# wifi-power.net
KiCad netlist of a schematic drawn in EAGLE
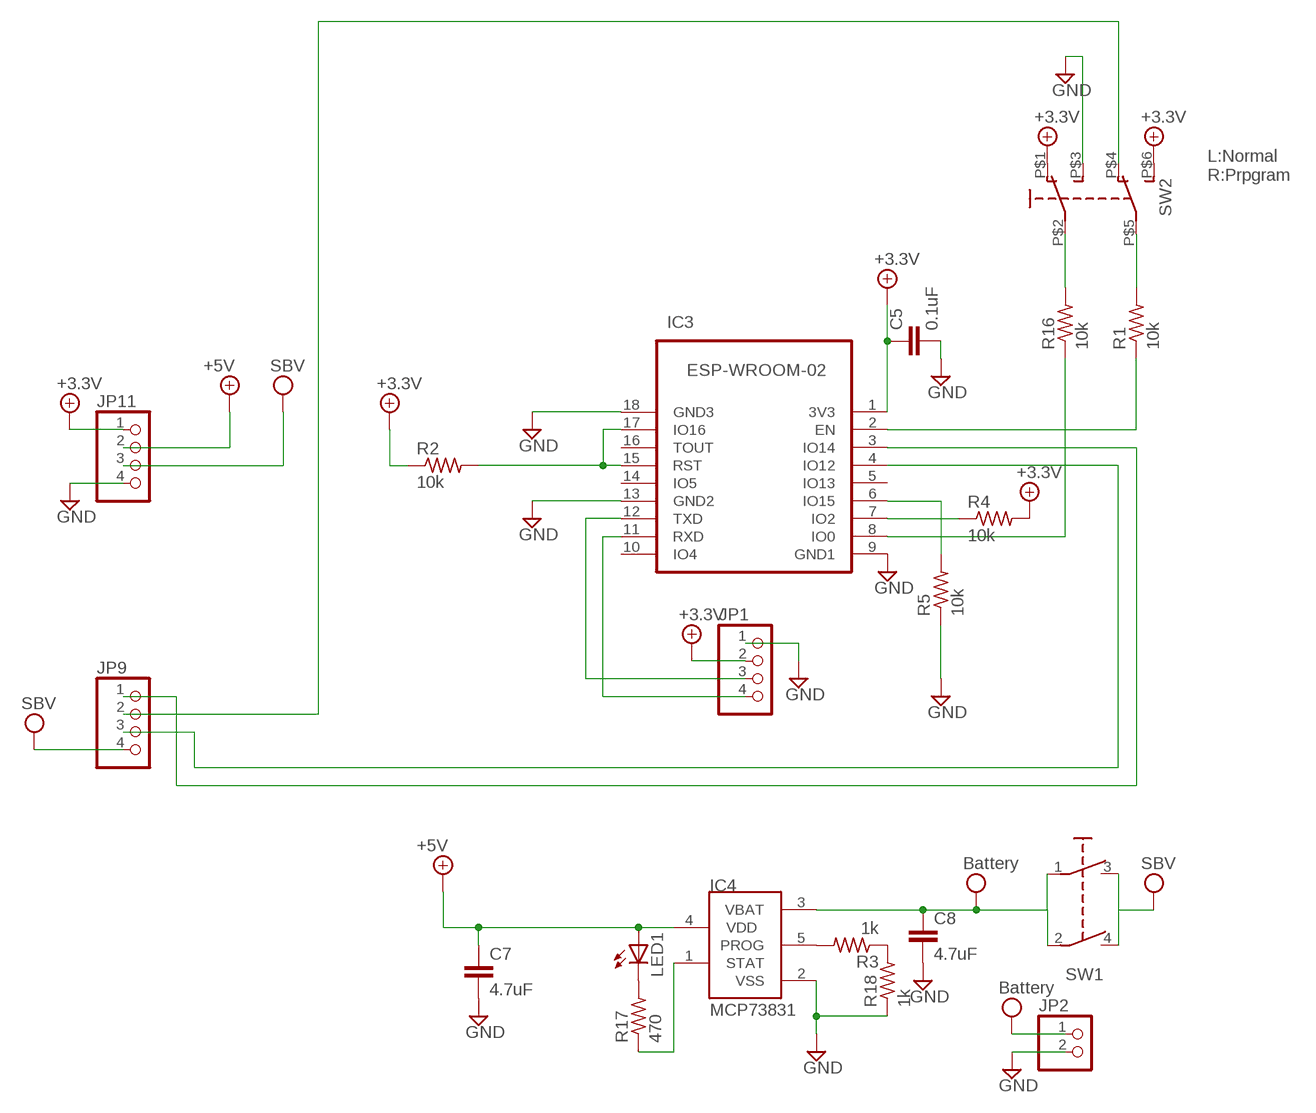
[diagram p0: schematic, sheet 1]

(export (version "E")
  (design (tool "Eeschema 10.0.6"))
  (components
    (comp (ref "C5")
      (value "0.1uF")
      (footprint "eagle-import:C0603K")
      (libsource (lib "eagle-import") (part "C-EUC0603K"))
    )
    (comp (ref "C7")
      (value "4.7uF")
      (footprint "eagle-import:C0603K")
      (libsource (lib "eagle-import") (part "C-EUC0603K"))
    )
    (comp (ref "C8")
      (value "4.7uF")
      (footprint "eagle-import:C0603K")
      (libsource (lib "eagle-import") (part "C-EUC0603K"))
    )
    (comp (ref "IC3")
      (value "ESP-WROOM-02")
      (footprint "eagle-import:FRONT-FACE")
      (libsource (lib "eagle-import") (part "ESP-WROOM-02FRONT-FACE"))
    )
    (comp (ref "IC4")
      (value "MCP73831")
      (footprint "eagle-import:SOT23-5L")
      (libsource (lib "eagle-import") (part "MCP73831"))
    )
    (comp (ref "JP1")
      (value "PINHD-1X4")
      (footprint "eagle-import:1X04")
      (libsource (lib "eagle-import") (part "PINHD-1X4"))
    )
    (comp (ref "JP2")
      (value "PINHD-1X2")
      (footprint "eagle-import:1X02")
      (libsource (lib "eagle-import") (part "PINHD-1X2"))
    )
    (comp (ref "JP9")
      (value "PINHD-1X4")
      (footprint "eagle-import:1X04")
      (libsource (lib "eagle-import") (part "PINHD-1X4"))
    )
    (comp (ref "JP11")
      (value "PINHD-1X4")
      (footprint "eagle-import:1X04")
      (libsource (lib "eagle-import") (part "PINHD-1X4"))
    )
    (comp (ref "LED1")
      (value "LG_T679-E1F1-1")
      (footprint "eagle-import:PLCC2")
      (libsource (lib "eagle-import") (part "_T679-?-1E1F1LG"))
    )
    (comp (ref "R1")
      (value "10k")
      (footprint "eagle-import:M0805")
      (libsource (lib "eagle-import") (part "R-US_M0805"))
    )
    (comp (ref "R2")
      (value "10k")
      (footprint "eagle-import:M0805")
      (libsource (lib "eagle-import") (part "R-US_M0805"))
    )
    (comp (ref "R3")
      (value "1k")
      (footprint "eagle-import:MINI_MELF-0102R")
      (libsource (lib "eagle-import") (part "R-US_MELF0102R"))
    )
    (comp (ref "R4")
      (value "10k")
      (footprint "eagle-import:M0805")
      (libsource (lib "eagle-import") (part "R-US_M0805"))
    )
    (comp (ref "R5")
      (value "10k")
      (footprint "eagle-import:M0805")
      (libsource (lib "eagle-import") (part "R-US_M0805"))
    )
    (comp (ref "R16")
      (value "10k")
      (footprint "eagle-import:M0805")
      (libsource (lib "eagle-import") (part "R-US_M0805"))
    )
    (comp (ref "R17")
      (value "470")
      (footprint "eagle-import:M0805")
      (libsource (lib "eagle-import") (part "R-US_M0805"))
    )
    (comp (ref "R18")
      (value "1k")
      (footprint "eagle-import:MINI_MELF-0102R")
      (libsource (lib "eagle-import") (part "R-US_MELF0102R"))
    )
    (comp (ref "SW1")
      (value "2X1S-SIDE-0.1INCH")
      (footprint "eagle-import:2X1SIDE-0.1INCH")
      (libsource (lib "eagle-import") (part "2X1S-SIDE-0.1INCH"))
    )
    (comp (ref "SW2")
      (value "MSS-22C02")
      (footprint "eagle-import:MSS-22C02")
      (libsource (lib "eagle-import") (part "MSS-22C02"))
    )
  )
  (nets
    (net (code "1") (name "+3.3V") (class "Default")
      (node (ref "C5") (pin "1") (pinfunction "1_1") (pintype "passive"))
      (node (ref "IC3") (pin "1") (pinfunction "3V3_1") (pintype "power_in"))
      (node (ref "JP1") (pin "2") (pinfunction "2_2") (pintype "passive"))
      (node (ref "JP11") (pin "1") (pinfunction "1_1") (pintype "passive"))
      (node (ref "R2") (pin "1") (pinfunction "1_1") (pintype "passive"))
      (node (ref "R4") (pin "2") (pinfunction "2_2") (pintype "passive"))
      (node (ref "SW2") (pin "P$1") (pinfunction "O_P$1") (pintype "passive"))
      (node (ref "SW2") (pin "P$6") (pinfunction "S1_P$6") (pintype "passive"))
    )
    (net (code "2") (name "+5V") (class "Default")
      (node (ref "C7") (pin "1") (pinfunction "1_1") (pintype "passive"))
      (node (ref "IC4") (pin "4") (pinfunction "VDD_4") (pintype "bidirectional"))
      (node (ref "JP11") (pin "2") (pinfunction "2_2") (pintype "passive"))
      (node (ref "LED1") (pin "A") (pinfunction "A_A") (pintype "passive"))
    )
    (net (code "3") (name "Battery") (class "Default")
      (node (ref "C8") (pin "1") (pinfunction "1_1") (pintype "passive"))
      (node (ref "IC4") (pin "3") (pinfunction "VBAT_3") (pintype "bidirectional"))
      (node (ref "JP2") (pin "1") (pinfunction "1_1") (pintype "passive"))
      (node (ref "SW1") (pin "1") (pinfunction "P_1") (pintype "passive"))
      (node (ref "SW1") (pin "2") (pinfunction "P1_2") (pintype "passive"))
    )
    (net (code "4") (name "GND") (class "Default")
      (node (ref "C5") (pin "2") (pinfunction "2_2") (pintype "passive"))
      (node (ref "C7") (pin "2") (pinfunction "2_2") (pintype "passive"))
      (node (ref "C8") (pin "2") (pinfunction "2_2") (pintype "passive"))
      (node (ref "IC3") (pin "13") (pinfunction "GND2_13") (pintype "power_in"))
      (node (ref "IC3") (pin "18") (pinfunction "GND3_18") (pintype "power_in"))
      (node (ref "IC3") (pin "9") (pinfunction "GND1_9") (pintype "power_in"))
      (node (ref "IC4") (pin "2") (pinfunction "VSS_2") (pintype "bidirectional"))
      (node (ref "JP1") (pin "1") (pinfunction "1_1") (pintype "passive"))
      (node (ref "JP11") (pin "4") (pinfunction "4_4") (pintype "passive"))
      (node (ref "JP2") (pin "2") (pinfunction "2_2") (pintype "passive"))
      (node (ref "R18") (pin "1") (pinfunction "1_1") (pintype "passive"))
      (node (ref "R5") (pin "1") (pinfunction "1_1") (pintype "passive"))
      (node (ref "SW2") (pin "P$3") (pinfunction "S_P$3") (pintype "passive"))
    )
    (net (code "5") (name "Net-(IC3-EN)") (class "Default")
      (node (ref "IC3") (pin "2") (pinfunction "EN_2") (pintype "bidirectional"))
      (node (ref "R1") (pin "1") (pinfunction "1_1") (pintype "passive"))
    )
    (net (code "6") (name "Net-(IC3-IO0)") (class "Default")
      (node (ref "IC3") (pin "8") (pinfunction "IO0_8") (pintype "bidirectional"))
      (node (ref "R16") (pin "1") (pinfunction "1_1") (pintype "passive"))
    )
    (net (code "7") (name "Net-(IC3-IO2)") (class "Default")
      (node (ref "IC3") (pin "7") (pinfunction "IO2_7") (pintype "bidirectional"))
      (node (ref "R4") (pin "1") (pinfunction "1_1") (pintype "passive"))
    )
    (net (code "8") (name "Net-(IC3-IO12)") (class "Default")
      (node (ref "IC3") (pin "4") (pinfunction "IO12_4") (pintype "bidirectional"))
      (node (ref "JP9") (pin "3") (pinfunction "3_3") (pintype "passive"))
    )
    (net (code "9") (name "Net-(IC3-IO14)") (class "Default")
      (node (ref "IC3") (pin "3") (pinfunction "IO14_3") (pintype "bidirectional"))
      (node (ref "JP9") (pin "1") (pinfunction "1_1") (pintype "passive"))
    )
    (net (code "10") (name "Net-(IC3-IO15)") (class "Default")
      (node (ref "IC3") (pin "6") (pinfunction "IO15_6") (pintype "bidirectional"))
      (node (ref "R5") (pin "2") (pinfunction "2_2") (pintype "passive"))
    )
    (net (code "11") (name "Net-(IC3-IO16)") (class "Default")
      (node (ref "IC3") (pin "15") (pinfunction "RST_15") (pintype "bidirectional"))
      (node (ref "IC3") (pin "17") (pinfunction "IO16_17") (pintype "bidirectional"))
      (node (ref "R2") (pin "2") (pinfunction "2_2") (pintype "passive"))
    )
    (net (code "12") (name "Net-(IC3-RXD)") (class "Default")
      (node (ref "IC3") (pin "11") (pinfunction "RXD_11") (pintype "bidirectional"))
      (node (ref "JP1") (pin "4") (pinfunction "4_4") (pintype "passive"))
    )
    (net (code "13") (name "Net-(IC3-TXD)") (class "Default")
      (node (ref "IC3") (pin "12") (pinfunction "TXD_12") (pintype "bidirectional"))
      (node (ref "JP1") (pin "3") (pinfunction "3_3") (pintype "passive"))
    )
    (net (code "14") (name "Net-(IC4-PROG)") (class "Default")
      (node (ref "IC4") (pin "5") (pinfunction "PROG_5") (pintype "bidirectional"))
      (node (ref "R3") (pin "2") (pinfunction "2_2") (pintype "passive"))
    )
    (net (code "15") (name "Net-(IC4-STAT)") (class "Default")
      (node (ref "IC4") (pin "1") (pinfunction "STAT_1") (pintype "bidirectional"))
      (node (ref "R17") (pin "1") (pinfunction "1_1") (pintype "passive"))
    )
    (net (code "16") (name "Net-(LED1-PadC)") (class "Default")
      (node (ref "LED1") (pin "C") (pinfunction "C_C") (pintype "passive"))
      (node (ref "R17") (pin "2") (pinfunction "2_2") (pintype "passive"))
    )
    (net (code "17") (name "Net-(R18-Pad2)") (class "Default")
      (node (ref "R18") (pin "2") (pinfunction "2_2") (pintype "passive"))
      (node (ref "R3") (pin "1") (pinfunction "1_1") (pintype "passive"))
    )
    (net (code "18") (name "Net-(SW2-O1)") (class "Default")
      (node (ref "JP9") (pin "2") (pinfunction "2_2") (pintype "passive"))
      (node (ref "SW2") (pin "P$4") (pinfunction "O1_P$4") (pintype "passive"))
    )
    (net (code "19") (name "Net-(SW2-P)") (class "Default")
      (node (ref "R16") (pin "2") (pinfunction "2_2") (pintype "passive"))
      (node (ref "SW2") (pin "P$2") (pinfunction "P_P$2") (pintype "passive"))
    )
    (net (code "20") (name "Net-(SW2-P1)") (class "Default")
      (node (ref "R1") (pin "2") (pinfunction "2_2") (pintype "passive"))
      (node (ref "SW2") (pin "P$5") (pinfunction "P1_P$5") (pintype "passive"))
    )
    (net (code "21") (name "SBV") (class "Default")
      (node (ref "JP11") (pin "3") (pinfunction "3_3") (pintype "passive"))
      (node (ref "JP9") (pin "4") (pinfunction "4_4") (pintype "passive"))
      (node (ref "SW1") (pin "3") (pinfunction "S_3") (pintype "passive"))
      (node (ref "SW1") (pin "4") (pinfunction "S1_4") (pintype "passive"))
    )
    (net (code "22") (name "unconnected-(IC3-IO4-Pad10)") (class "Default")
      (node (ref "IC3") (pin "10") (pinfunction "IO4_10") (pintype "bidirectional"))
    )
    (net (code "23") (name "unconnected-(IC3-IO5-Pad14)") (class "Default")
      (node (ref "IC3") (pin "14") (pinfunction "IO5_14") (pintype "open_collector"))
    )
    (net (code "24") (name "unconnected-(IC3-IO13-Pad5)") (class "Default")
      (node (ref "IC3") (pin "5") (pinfunction "IO13_5") (pintype "bidirectional"))
    )
    (net (code "25") (name "unconnected-(IC3-TOUT-Pad16)") (class "Default")
      (node (ref "IC3") (pin "16") (pinfunction "TOUT_16") (pintype "bidirectional"))
    )
  )
)
